# MCU_USB.net
KiCad netlist of a schematic drawn in Altium Designer
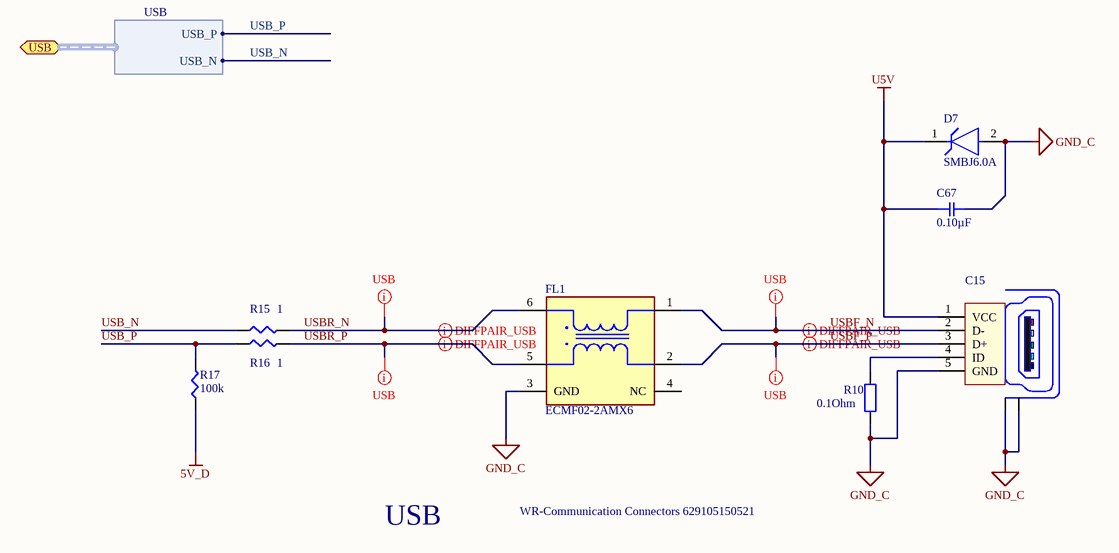
[diagram p0: MCU_USB.SchDoc]

(export (version "E")
  (design (tool "Eeschema 10.0.6"))
  (components
    (comp (ref "C15")
      (value "WR-Communication Connectors 629105150521")
      (footprint "629105150521")
      (description "WR-COM_USB_Micro Type B_Horizontal_SMT")
      (fields
        (field (name "MANUFACTURER") "Würth Elektronik eiSos GmbH")
        (field (name "PARTNO") "629105150521")
        (field (name "CREATED BY") "Karrer Zheng")
      )
      (libsource (lib "629105136821_Altium_629105136821_rev16d") (part "WR-Communication Connectors 629105150521"))
    )
    (comp (ref "C67")
      (value "0.10µF")
      (footprint "SMD-0805C")
      (description "CAP CER 0.1UF 100V X7R 0805")
      (fields
        (field (name "DIGI-KEY PART NUMBER") "490-5825-1-ND")
        (field (name "PART NUMBER") "GCJ21BR72A104KA01L")
      )
      (libsource (lib "capacitor_murata_0805") (part "GCJ21BR72A104KA01L"))
    )
    (comp (ref "D7")
      (value "SMBJ6.0A")
      (footprint "FP-SMBJ-MFG")
      (description "TVS DIODE 6V 10.3V DO214AA")
      (fields
        (field (name "MANUFACTURER") "Littelfuse Inc")
        (field (name "OCTOPART") "https://octopart.com/smbj6.0a-littelfuse-66100")
      )
      (libsource (lib "Altium Content Vault") (part "f813f71cba58e380607f5dd3caf9714"))
    )
    (comp (ref "FL1")
      (value "ECMF02-2AMX6")
      (footprint "FP-QFN-6L-MFG")
      (description "CMC 200MA 2LN SMD ESD")
      (fields
        (field (name "MANUFACTURER") "STMicroelectronics")
        (field (name "OCTOPART") "https://octopart.com/ecmf02-2amx6-stmicroelectronics-44353078")
      )
      (libsource (lib "Altium Content Vault") (part "8feffc7f24acfb857157da90e949b57"))
    )
    (comp (ref "R10")
      (value "0.1Ohm")
      (footprint "WRIS-KSKE_0603_H=0.45mm")
      (description "WRIS-KSKE Thick Film Resistors, size 0603, 0.1Ohm, +/-1%, 0.25W")
      (fields (field (name "PART NUMBER") "560050316001") (field (name "PUBLISHER") "Wurth Elektronik"))
      (libsource (lib "Altium_WRIS-KSKE_rev19a") (part "560050316001"))
    )
    (comp (ref "R15")
      (value "1")
      (footprint "SMD-0603-RES")
      (description "RES SMD 1 OHM 1% 1/4W 0603")
      (fields (field (name "PART NUMBER") "ERJ-3BQF1R0V") (field (name "DIGI-KEY PART NUMBER") "P17371CT-ND"))
      (libsource (lib "Panasonic_ERJ_0603") (part "ERJ-3BQF1R0V"))
    )
    (comp (ref "R16")
      (value "1")
      (footprint "SMD-0603-RES")
      (description "RES SMD 1 OHM 1% 1/4W 0603")
      (fields (field (name "PART NUMBER") "ERJ-3BQF1R0V") (field (name "DIGI-KEY PART NUMBER") "P17371CT-ND"))
      (libsource (lib "Panasonic_ERJ_0603") (part "ERJ-3BQF1R0V"))
    )
    (comp (ref "R17")
      (value "100k")
      (footprint "SMD-0603-RES")
      (description "RES SMD 100K OHM 1% 1/10W 0603")
      (fields
        (field (name "PART NUMBER") "ERJ-3EKF1003V")
        (field (name "DIGI-KEY PART NUMBER") "P100KHCT-ND")
      )
      (libsource (lib "Panasonic_ERJ_0603") (part "ERJ-3EKF1003V"))
    )
  )
  (nets
    (net (code "2") (name "/USBF_N") (class "Default")
      (node (ref "C15") (pin "2") (pinfunction "D-_2") (pintype "passive"))
      (node (ref "FL1") (pin "1") (pinfunction "D+_1") (pintype "passive"))
    )
    (net (code "3") (name "/USBF_P") (class "Default")
      (node (ref "C15") (pin "3") (pinfunction "D+_3") (pintype "passive"))
      (node (ref "FL1") (pin "2") (pinfunction "D-_2") (pintype "passive"))
    )
    (net (code "4") (name "/USBR_N") (class "Default")
      (node (ref "FL1") (pin "6") (pinfunction "D+_6") (pintype "passive"))
      (node (ref "R15") (pin "2") (pinfunction "2_2") (pintype "passive"))
    )
    (net (code "5") (name "/USBR_P") (class "Default")
      (node (ref "FL1") (pin "5") (pinfunction "D-_5") (pintype "passive"))
      (node (ref "R16") (pin "2") (pinfunction "2_2") (pintype "passive"))
    )
    (net (code "6") (name "/USB_N") (class "Default")
      (node (ref "R15") (pin "1") (pinfunction "1_1") (pintype "passive"))
    )
    (net (code "7") (name "/USB_P") (class "Default")
      (node (ref "R16") (pin "1") (pinfunction "1_1") (pintype "passive"))
      (node (ref "R17") (pin "2") (pinfunction "2_2") (pintype "passive"))
    )
    (net (code "9") (name "5V_D") (class "Default")
      (node (ref "R17") (pin "1") (pinfunction "1_1") (pintype "passive"))
    )
    (net (code "10") (name "GND_C") (class "Default")
      (node (ref "C15") (pin "5") (pinfunction "GND_5") (pintype "passive"))
      (node (ref "C15") (pin "Z1") (pinfunction "Shield_Z1") (pintype "passive"))
      (node (ref "C15") (pin "Z2") (pinfunction "Shield_Z2") (pintype "passive"))
      (node (ref "C67") (pin "2") (pinfunction "2_2") (pintype "passive"))
      (node (ref "D7") (pin "2") (pinfunction "A_2") (pintype "passive"))
      (node (ref "FL1") (pin "3") (pinfunction "GND_3") (pintype "power_in"))
      (node (ref "R10") (pin "2") (pinfunction "2_2") (pintype "passive"))
    )
    (net (code "11") (name "Net-(C15-ID)") (class "Default")
      (node (ref "C15") (pin "4") (pinfunction "ID_4") (pintype "passive"))
      (node (ref "R10") (pin "1") (pinfunction "1_1") (pintype "passive"))
    )
    (net (code "12") (name "U5V") (class "Default")
      (node (ref "C15") (pin "1") (pinfunction "VCC_1") (pintype "passive"))
      (node (ref "C67") (pin "1") (pinfunction "1_1") (pintype "passive"))
      (node (ref "D7") (pin "1") (pinfunction "C_1") (pintype "passive"))
    )
    (net (code "13") (name "unconnected-(FL1-NC-Pad4)") (class "Default")
      (node (ref "FL1") (pin "4") (pinfunction "NC_4") (pintype "passive"))
    )
  )
)
